# DiffController.net
KiCad netlist of a schematic drawn in EAGLE
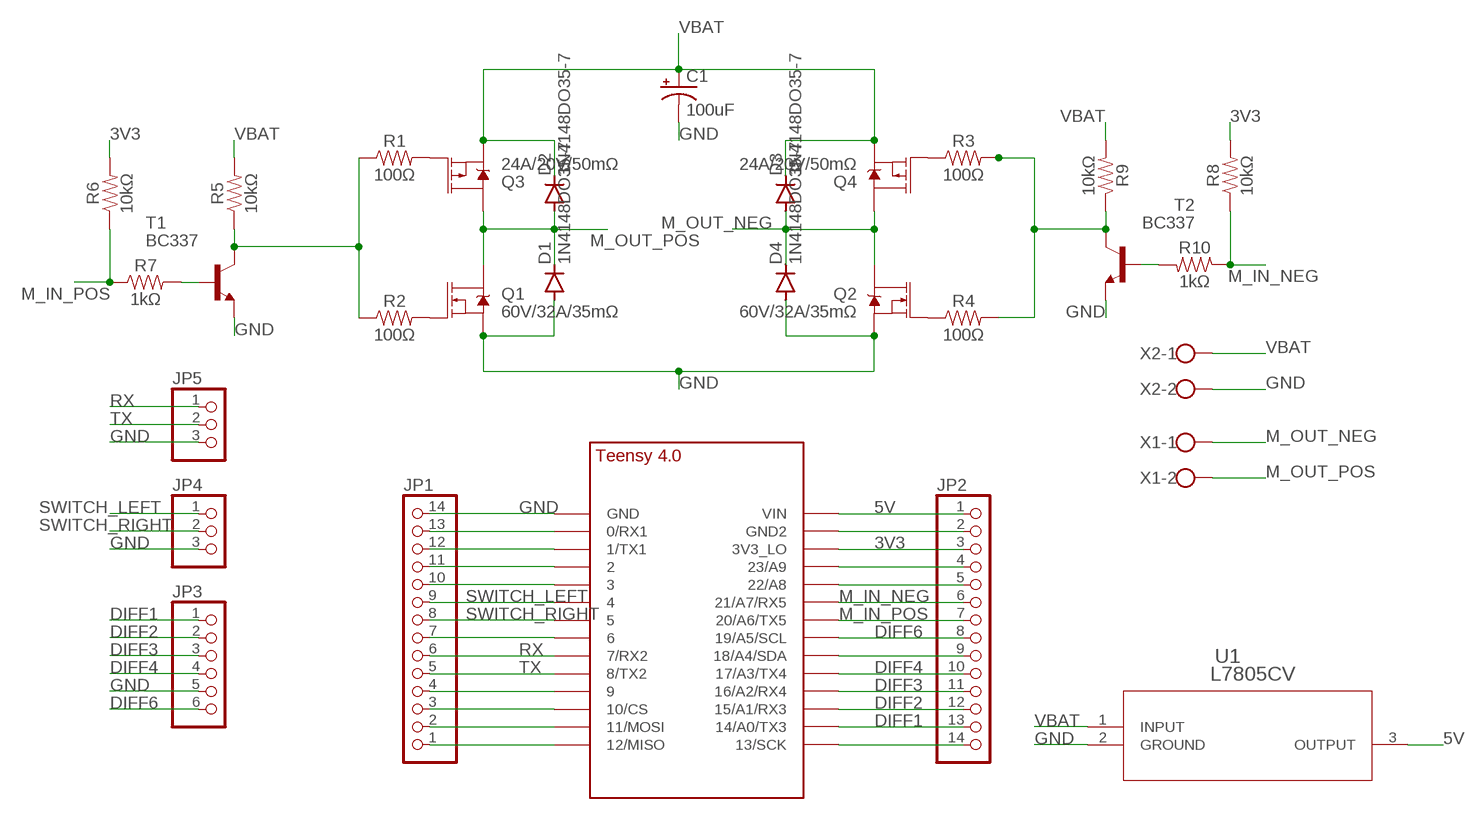
[diagram p0: schematic, sheet 1]

(export (version "E")
  (design (tool "Eeschema 10.0.6"))
  (components
    (comp (ref "C1")
      (value "100uF")
      (footprint "eagle-import:CPOL-RADIAL-2.5MM-6.5MM")
      (libsource (lib "eagle-import") (part "100UF-POLAR-RADIAL-2.5MM-25V-20%"))
    )
    (comp (ref "D1")
      (value "1N4148DO35-7")
      (footprint "eagle-import:DO35-7")
      (libsource (lib "eagle-import") (part "1N4148DO35-7"))
    )
    (comp (ref "D2")
      (value "1N4148DO35-7")
      (footprint "eagle-import:DO35-7")
      (libsource (lib "eagle-import") (part "1N4148DO35-7"))
    )
    (comp (ref "D3")
      (value "1N4148DO35-7")
      (footprint "eagle-import:DO35-7")
      (libsource (lib "eagle-import") (part "1N4148DO35-7"))
    )
    (comp (ref "D4")
      (value "1N4148DO35-7")
      (footprint "eagle-import:DO35-7")
      (libsource (lib "eagle-import") (part "1N4148DO35-7"))
    )
    (comp (ref "JP1")
      (value "PINHD-1X14")
      (footprint "eagle-import:1X14")
      (libsource (lib "eagle-import") (part "PINHD-1X14"))
    )
    (comp (ref "JP2")
      (value "PINHD-1X14")
      (footprint "eagle-import:1X14")
      (libsource (lib "eagle-import") (part "PINHD-1X14"))
    )
    (comp (ref "JP3")
      (value "PINHD-1X6")
      (footprint "eagle-import:1X06")
      (libsource (lib "eagle-import") (part "PINHD-1X6"))
    )
    (comp (ref "JP4")
      (value "PINHD-1X3")
      (footprint "eagle-import:1X03")
      (libsource (lib "eagle-import") (part "PINHD-1X3"))
    )
    (comp (ref "JP5")
      (value "PINHD-1X3")
      (footprint "eagle-import:1X03")
      (libsource (lib "eagle-import") (part "PINHD-1X3"))
    )
    (comp (ref "Q1")
      (value "60V/32A/35mΩ")
      (footprint "eagle-import:TO220V")
      (libsource (lib "eagle-import") (part "MOSFET-NCH-FQP30N06L"))
    )
    (comp (ref "Q2")
      (value "60V/32A/35mΩ")
      (footprint "eagle-import:TO220V")
      (libsource (lib "eagle-import") (part "MOSFET-NCH-FQP30N06L"))
    )
    (comp (ref "Q3")
      (value "24A/20V/50mΩ")
      (footprint "eagle-import:TO220V")
      (libsource (lib "eagle-import") (part "MOSFET_PCH-NDP6020P"))
    )
    (comp (ref "Q4")
      (value "24A/20V/50mΩ")
      (footprint "eagle-import:TO220V")
      (libsource (lib "eagle-import") (part "MOSFET_PCH-NDP6020P"))
    )
    (comp (ref "R1")
      (value "100Ω")
      (footprint "eagle-import:AXIAL-0.3")
      (libsource (lib "eagle-import") (part "RESISTORAXIAL-0.3"))
    )
    (comp (ref "R2")
      (value "100Ω")
      (footprint "eagle-import:AXIAL-0.3")
      (libsource (lib "eagle-import") (part "RESISTORAXIAL-0.3"))
    )
    (comp (ref "R3")
      (value "100Ω")
      (footprint "eagle-import:AXIAL-0.3")
      (libsource (lib "eagle-import") (part "RESISTORAXIAL-0.3"))
    )
    (comp (ref "R4")
      (value "100Ω")
      (footprint "eagle-import:AXIAL-0.3")
      (libsource (lib "eagle-import") (part "RESISTORAXIAL-0.3"))
    )
    (comp (ref "R5")
      (value "10kΩ")
      (footprint "eagle-import:AXIAL-0.3")
      (libsource (lib "eagle-import") (part "RESISTORAXIAL-0.3"))
    )
    (comp (ref "R6")
      (value "10kΩ")
      (footprint "eagle-import:AXIAL-0.3")
      (libsource (lib "eagle-import") (part "RESISTORAXIAL-0.3"))
    )
    (comp (ref "R7")
      (value "1kΩ")
      (footprint "eagle-import:AXIAL-0.3")
      (libsource (lib "eagle-import") (part "RESISTORAXIAL-0.3"))
    )
    (comp (ref "R8")
      (value "10kΩ")
      (footprint "eagle-import:AXIAL-0.3")
      (libsource (lib "eagle-import") (part "RESISTORAXIAL-0.3"))
    )
    (comp (ref "R9")
      (value "10kΩ")
      (footprint "eagle-import:AXIAL-0.3")
      (libsource (lib "eagle-import") (part "RESISTORAXIAL-0.3"))
    )
    (comp (ref "R10")
      (value "1kΩ")
      (footprint "eagle-import:AXIAL-0.3")
      (libsource (lib "eagle-import") (part "RESISTORAXIAL-0.3"))
    )
    (comp (ref "T1")
      (value "BC337")
      (footprint "eagle-import:TO92")
      (libsource (lib "eagle-import") (part "BC337"))
    )
    (comp (ref "T2")
      (value "BC337")
      (footprint "eagle-import:TO92")
      (libsource (lib "eagle-import") (part "BC337"))
    )
    (comp (ref "U$1")
      (value "TEENSY_4.0_SIMPLE")
      (footprint "eagle-import:TEENSY_4.0_SIMPLE")
      (libsource (lib "eagle-import") (part "TEENSY_4.0_SIMPLE"))
    )
    (comp (ref "U1")
      (value "L7805CV")
      (footprint "eagle-import:TO-220_STM")
      (libsource (lib "eagle-import") (part "L7805CV"))
    )
    (comp (ref "X1")
      (value "W237-102")
      (footprint "eagle-import:W237-102")
      (fields (field (name "MPN") "237-102"))
      (libsource (lib "eagle-import") (part "W237-102"))
    )
    (comp (ref "X2")
      (value "W237-102")
      (footprint "eagle-import:W237-102")
      (fields (field (name "MPN") "237-102"))
      (libsource (lib "eagle-import") (part "W237-102"))
    )
  )
  (nets
    (net (code "1") (name "/3V3") (class "Default")
      (node (ref "JP2") (pin "3") (pinfunction "3_3") (pintype "passive"))
      (node (ref "R6") (pin "P$2") (pinfunction "2_P$2") (pintype "passive"))
      (node (ref "R8") (pin "P$2") (pinfunction "2_P$2") (pintype "passive"))
      (node (ref "U$1") (pin "3V3_LO") (pinfunction "3V3_LO_3V3_LO") (pintype "bidirectional"))
    )
    (net (code "2") (name "/5V") (class "Default")
      (node (ref "JP2") (pin "1") (pinfunction "1_1") (pintype "passive"))
      (node (ref "U$1") (pin "VIN") (pinfunction "VIN_VIN") (pintype "bidirectional"))
      (node (ref "U1") (pin "3") (pinfunction "OUTPUT_3") (pintype "output"))
    )
    (net (code "3") (name "/DIFF1") (class "Default")
      (node (ref "JP2") (pin "13") (pinfunction "13_13") (pintype "passive"))
      (node (ref "JP3") (pin "1") (pinfunction "1_1") (pintype "passive"))
      (node (ref "U$1") (pin "14/A0") (pinfunction "14/A0/TX3_14/A0") (pintype "bidirectional"))
    )
    (net (code "4") (name "/DIFF2") (class "Default")
      (node (ref "JP2") (pin "12") (pinfunction "12_12") (pintype "passive"))
      (node (ref "JP3") (pin "2") (pinfunction "2_2") (pintype "passive"))
      (node (ref "U$1") (pin "15/A1") (pinfunction "15/A1/RX3_15/A1") (pintype "bidirectional"))
    )
    (net (code "5") (name "/DIFF3") (class "Default")
      (node (ref "JP2") (pin "11") (pinfunction "11_11") (pintype "passive"))
      (node (ref "JP3") (pin "3") (pinfunction "3_3") (pintype "passive"))
      (node (ref "U$1") (pin "16/A2") (pinfunction "16/A2/RX4_16/A2") (pintype "bidirectional"))
    )
    (net (code "6") (name "/DIFF4") (class "Default")
      (node (ref "JP2") (pin "10") (pinfunction "10_10") (pintype "passive"))
      (node (ref "JP3") (pin "4") (pinfunction "4_4") (pintype "passive"))
      (node (ref "U$1") (pin "17/A3") (pinfunction "17/A3/TX4_17/A3") (pintype "bidirectional"))
    )
    (net (code "7") (name "/DIFF6") (class "Default")
      (node (ref "JP2") (pin "8") (pinfunction "8_8") (pintype "passive"))
      (node (ref "JP3") (pin "6") (pinfunction "6_6") (pintype "passive"))
      (node (ref "U$1") (pin "19/A5/SCL") (pinfunction "19/A5/SCL_19/A5/SCL") (pintype "bidirectional"))
    )
    (net (code "8") (name "/GND") (class "Default")
      (node (ref "C1") (pin "2") (pinfunction "-_2") (pintype "passive"))
      (node (ref "D1") (pin "A") (pinfunction "A_A") (pintype "passive"))
      (node (ref "D4") (pin "A") (pinfunction "A_A") (pintype "passive"))
      (node (ref "JP1") (pin "14") (pinfunction "14_14") (pintype "passive"))
      (node (ref "JP3") (pin "5") (pinfunction "5_5") (pintype "passive"))
      (node (ref "JP4") (pin "3") (pinfunction "3_3") (pintype "passive"))
      (node (ref "JP5") (pin "3") (pinfunction "3_3") (pintype "passive"))
      (node (ref "Q1") (pin "3") (pinfunction "S_3") (pintype "bidirectional"))
      (node (ref "Q2") (pin "3") (pinfunction "S_3") (pintype "bidirectional"))
      (node (ref "T1") (pin "1") (pinfunction "E_1") (pintype "passive"))
      (node (ref "T2") (pin "1") (pinfunction "E_1") (pintype "passive"))
      (node (ref "U$1") (pin "GND") (pinfunction "GND_GND") (pintype "bidirectional"))
      (node (ref "U1") (pin "2") (pinfunction "GROUND_2") (pintype "passive"))
      (node (ref "X2") (pin "2") (pinfunction "KL_2") (pintype "passive"))
    )
    (net (code "9") (name "/M_IN_NEG") (class "Default")
      (node (ref "JP2") (pin "6") (pinfunction "6_6") (pintype "passive"))
      (node (ref "R10") (pin "P$1") (pinfunction "1_P$1") (pintype "passive"))
      (node (ref "R8") (pin "P$1") (pinfunction "1_P$1") (pintype "passive"))
      (node (ref "U$1") (pin "21/A7") (pinfunction "21/A7/RX5_21/A7") (pintype "bidirectional"))
    )
    (net (code "10") (name "/M_IN_POS") (class "Default")
      (node (ref "JP2") (pin "7") (pinfunction "7_7") (pintype "passive"))
      (node (ref "R6") (pin "P$1") (pinfunction "1_P$1") (pintype "passive"))
      (node (ref "R7") (pin "P$1") (pinfunction "1_P$1") (pintype "passive"))
      (node (ref "U$1") (pin "20/A6") (pinfunction "20/A6/TX5_20/A6") (pintype "bidirectional"))
    )
    (net (code "11") (name "/M_OUT_NEG") (class "Default")
      (node (ref "D3") (pin "A") (pinfunction "A_A") (pintype "passive"))
      (node (ref "D4") (pin "C") (pinfunction "C_C") (pintype "passive"))
      (node (ref "Q2") (pin "2") (pinfunction "D_2") (pintype "bidirectional"))
      (node (ref "Q4") (pin "2") (pinfunction "D_2") (pintype "bidirectional"))
      (node (ref "X1") (pin "1") (pinfunction "KL_1") (pintype "passive"))
    )
    (net (code "12") (name "/M_OUT_POS") (class "Default")
      (node (ref "D1") (pin "C") (pinfunction "C_C") (pintype "passive"))
      (node (ref "D2") (pin "A") (pinfunction "A_A") (pintype "passive"))
      (node (ref "Q1") (pin "2") (pinfunction "D_2") (pintype "bidirectional"))
      (node (ref "Q3") (pin "2") (pinfunction "D_2") (pintype "bidirectional"))
      (node (ref "X1") (pin "2") (pinfunction "KL_2") (pintype "passive"))
    )
    (net (code "13") (name "/RX") (class "Default")
      (node (ref "JP1") (pin "6") (pinfunction "6_6") (pintype "passive"))
      (node (ref "JP5") (pin "1") (pinfunction "1_1") (pintype "passive"))
      (node (ref "U$1") (pin "7") (pinfunction "7/RX2_7") (pintype "bidirectional"))
    )
    (net (code "14") (name "/SWITCH_LEFT") (class "Default")
      (node (ref "JP1") (pin "9") (pinfunction "9_9") (pintype "passive"))
      (node (ref "JP4") (pin "1") (pinfunction "1_1") (pintype "passive"))
      (node (ref "U$1") (pin "4/CANRX") (pinfunction "4_4/CANRX") (pintype "bidirectional"))
    )
    (net (code "15") (name "/SWITCH_RIGHT") (class "Default")
      (node (ref "JP1") (pin "8") (pinfunction "8_8") (pintype "passive"))
      (node (ref "JP4") (pin "2") (pinfunction "2_2") (pintype "passive"))
      (node (ref "U$1") (pin "5") (pinfunction "5_5") (pintype "bidirectional"))
    )
    (net (code "16") (name "/TX") (class "Default")
      (node (ref "JP1") (pin "5") (pinfunction "5_5") (pintype "passive"))
      (node (ref "JP5") (pin "2") (pinfunction "2_2") (pintype "passive"))
      (node (ref "U$1") (pin "8") (pinfunction "8/TX2_8") (pintype "bidirectional"))
    )
    (net (code "17") (name "/VBAT") (class "Default")
      (node (ref "C1") (pin "1") (pinfunction "+_1") (pintype "passive"))
      (node (ref "D2") (pin "C") (pinfunction "C_C") (pintype "passive"))
      (node (ref "D3") (pin "C") (pinfunction "C_C") (pintype "passive"))
      (node (ref "Q3") (pin "3") (pinfunction "S_3") (pintype "bidirectional"))
      (node (ref "Q4") (pin "3") (pinfunction "S_3") (pintype "bidirectional"))
      (node (ref "R5") (pin "P$2") (pinfunction "2_P$2") (pintype "passive"))
      (node (ref "R9") (pin "P$2") (pinfunction "2_P$2") (pintype "passive"))
      (node (ref "U1") (pin "1") (pinfunction "INPUT_1") (pintype "input"))
      (node (ref "X2") (pin "1") (pinfunction "KL_1") (pintype "passive"))
    )
    (net (code "18") (name "Net-(JP1-Pad1)") (class "Default")
      (node (ref "JP1") (pin "1") (pinfunction "1_1") (pintype "passive"))
      (node (ref "U$1") (pin "12/MISO") (pinfunction "12/MISO_12/MISO") (pintype "bidirectional"))
    )
    (net (code "19") (name "Net-(JP1-Pad2)") (class "Default")
      (node (ref "JP1") (pin "2") (pinfunction "2_2") (pintype "passive"))
      (node (ref "U$1") (pin "11/MOSI") (pinfunction "11/MOSI_11/MOSI") (pintype "bidirectional"))
    )
    (net (code "20") (name "Net-(JP1-Pad3)") (class "Default")
      (node (ref "JP1") (pin "3") (pinfunction "3_3") (pintype "passive"))
      (node (ref "U$1") (pin "10/CS") (pinfunction "10/CS_10/CS") (pintype "bidirectional"))
    )
    (net (code "21") (name "Net-(JP1-Pad7)") (class "Default")
      (node (ref "JP1") (pin "7") (pinfunction "7_7") (pintype "passive"))
      (node (ref "U$1") (pin "6") (pinfunction "6_6") (pintype "bidirectional"))
    )
    (net (code "22") (name "Net-(JP1-Pad11)") (class "Default")
      (node (ref "JP1") (pin "11") (pinfunction "11_11") (pintype "passive"))
      (node (ref "U$1") (pin "2") (pinfunction "2_2") (pintype "bidirectional"))
    )
    (net (code "23") (name "Net-(JP2-Pad2)") (class "Default")
      (node (ref "JP2") (pin "2") (pinfunction "2_2") (pintype "passive"))
      (node (ref "U$1") (pin "GND2") (pinfunction "GND2_GND2") (pintype "bidirectional"))
    )
    (net (code "24") (name "Net-(JP2-Pad4)") (class "Default")
      (node (ref "JP2") (pin "4") (pinfunction "4_4") (pintype "passive"))
      (node (ref "U$1") (pin "23/A9") (pinfunction "23/A9_23/A9") (pintype "bidirectional"))
    )
    (net (code "25") (name "Net-(JP2-Pad5)") (class "Default")
      (node (ref "JP2") (pin "5") (pinfunction "5_5") (pintype "passive"))
      (node (ref "U$1") (pin "22/A8") (pinfunction "22/A8_22/A8") (pintype "bidirectional"))
    )
    (net (code "26") (name "Net-(JP2-Pad9)") (class "Default")
      (node (ref "JP2") (pin "9") (pinfunction "9_9") (pintype "passive"))
      (node (ref "U$1") (pin "18/A4/SDA") (pinfunction "18/A4/SDA_18/A4/SDA") (pintype "bidirectional"))
    )
    (net (code "27") (name "Net-(JP2-Pad14)") (class "Default")
      (node (ref "JP2") (pin "14") (pinfunction "14_14") (pintype "passive"))
      (node (ref "U$1") (pin "13/SCK") (pinfunction "13/SCK_13/SCK") (pintype "bidirectional"))
    )
    (net (code "28") (name "Net-(Q1-G)") (class "Default")
      (node (ref "Q1") (pin "1") (pinfunction "G_1") (pintype "bidirectional"))
      (node (ref "R2") (pin "P$2") (pinfunction "2_P$2") (pintype "passive"))
    )
    (net (code "29") (name "Net-(Q2-G)") (class "Default")
      (node (ref "Q2") (pin "1") (pinfunction "G_1") (pintype "bidirectional"))
      (node (ref "R4") (pin "P$1") (pinfunction "1_P$1") (pintype "passive"))
    )
    (net (code "30") (name "Net-(Q3-G)") (class "Default")
      (node (ref "Q3") (pin "1") (pinfunction "G_1") (pintype "bidirectional"))
      (node (ref "R1") (pin "P$2") (pinfunction "2_P$2") (pintype "passive"))
    )
    (net (code "31") (name "Net-(Q4-G)") (class "Default")
      (node (ref "Q4") (pin "1") (pinfunction "G_1") (pintype "bidirectional"))
      (node (ref "R3") (pin "P$1") (pinfunction "1_P$1") (pintype "passive"))
    )
    (net (code "32") (name "Net-(R1-1)") (class "Default")
      (node (ref "R1") (pin "P$1") (pinfunction "1_P$1") (pintype "passive"))
      (node (ref "R2") (pin "P$1") (pinfunction "1_P$1") (pintype "passive"))
      (node (ref "R5") (pin "P$1") (pinfunction "1_P$1") (pintype "passive"))
      (node (ref "T1") (pin "3") (pinfunction "C_3") (pintype "passive"))
    )
    (net (code "33") (name "Net-(R3-2)") (class "Default")
      (node (ref "R3") (pin "P$2") (pinfunction "2_P$2") (pintype "passive"))
      (node (ref "R4") (pin "P$2") (pinfunction "2_P$2") (pintype "passive"))
      (node (ref "R9") (pin "P$1") (pinfunction "1_P$1") (pintype "passive"))
      (node (ref "T2") (pin "3") (pinfunction "C_3") (pintype "passive"))
    )
    (net (code "34") (name "Net-(R7-2)") (class "Default")
      (node (ref "R7") (pin "P$2") (pinfunction "2_P$2") (pintype "passive"))
      (node (ref "T1") (pin "2") (pinfunction "B_2") (pintype "passive"))
    )
    (net (code "35") (name "Net-(R10-2)") (class "Default")
      (node (ref "R10") (pin "P$2") (pinfunction "2_P$2") (pintype "passive"))
      (node (ref "T2") (pin "2") (pinfunction "B_2") (pintype "passive"))
    )
    (net (code "36") (name "Net-(U$1-0{slash}RX1)") (class "Default")
      (node (ref "JP1") (pin "13") (pinfunction "13_13") (pintype "passive"))
      (node (ref "U$1") (pin "0/RX") (pinfunction "0/RX1_0/RX") (pintype "bidirectional"))
    )
    (net (code "37") (name "Net-(U$1-1{slash}TX1)") (class "Default")
      (node (ref "JP1") (pin "12") (pinfunction "12_12") (pintype "passive"))
      (node (ref "U$1") (pin "1/TX") (pinfunction "1/TX1_1/TX") (pintype "bidirectional"))
    )
    (net (code "38") (name "Net-(U$1-3)") (class "Default")
      (node (ref "JP1") (pin "10") (pinfunction "10_10") (pintype "passive"))
      (node (ref "U$1") (pin "3/CANTX") (pinfunction "3_3/CANTX") (pintype "bidirectional"))
    )
    (net (code "39") (name "Net-(U$1-9)") (class "Default")
      (node (ref "JP1") (pin "4") (pinfunction "4_4") (pintype "passive"))
      (node (ref "U$1") (pin "9/CS") (pinfunction "9_9/CS") (pintype "bidirectional"))
    )
  )
)
